# POTENCIOMETRO.net
KiCad netlist of a schematic drawn in EAGLE
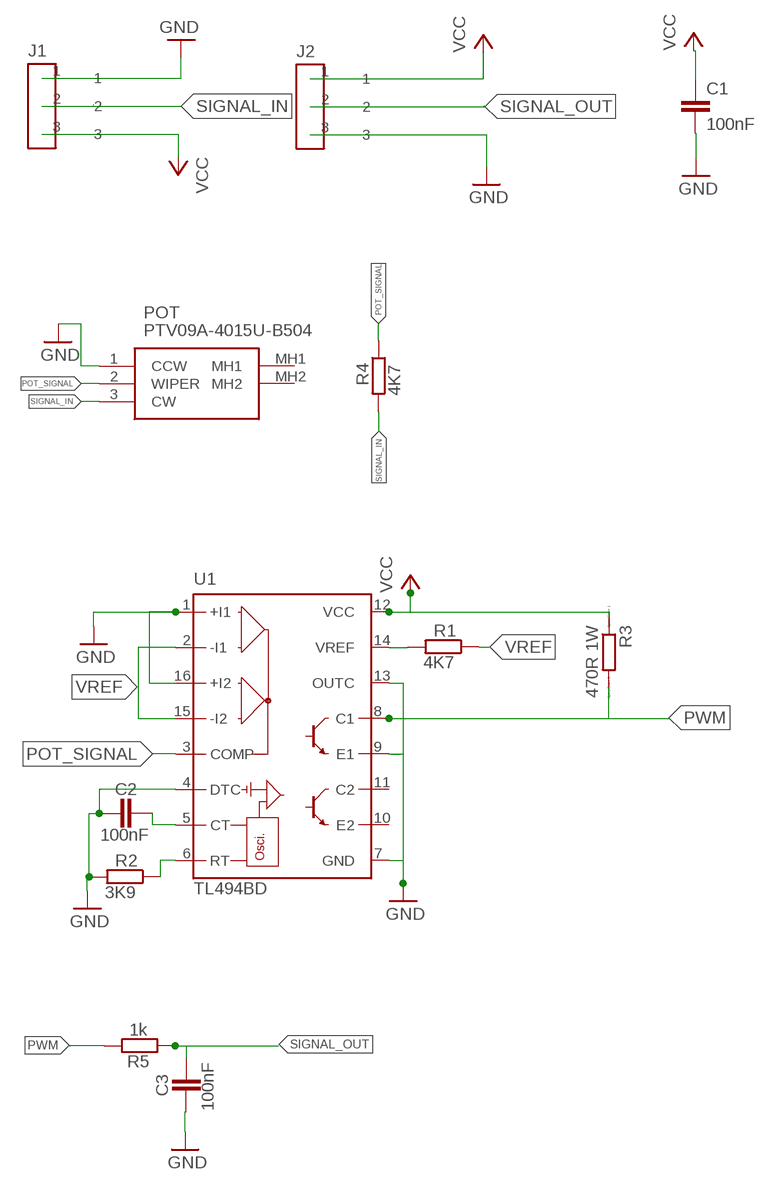
[diagram p0: schematic, sheet 1]

(export (version "E")
  (design (tool "Eeschema 10.0.6"))
  (components
    (comp (ref "C1")
      (value "100nF")
      (footprint "eagle-import:C0805")
      (libsource (lib "eagle-import") (part "C-EUC0805"))
    )
    (comp (ref "C2")
      (value "100nF")
      (footprint "eagle-import:C0805")
      (libsource (lib "eagle-import") (part "C-EUC0805"))
    )
    (comp (ref "C3")
      (value "100nF")
      (footprint "eagle-import:C0805")
      (libsource (lib "eagle-import") (part "C-EUC0805"))
    )
    (comp (ref "J1")
      (value "CONECTOR_MACHO")
      (footprint "eagle-import:3CONECTOR")
      (libsource (lib "eagle-import") (part "CONECTOR_MACHO"))
    )
    (comp (ref "J2")
      (value "CONECTOR_FEMEA")
      (footprint "eagle-import:3CONECTOR")
      (libsource (lib "eagle-import") (part "CONECTOR_FEMEA"))
    )
    (comp (ref "POT")
      (value "PTV09A-4015U-B504")
      (footprint "eagle-import:PTV09A4015UB104")
      (fields (field (name "MOUSER_PART_NUMBER") "652-PTV09A-4015UB504"))
      (libsource (lib "eagle-import") (part "PTV09A-4015U-B504"))
    )
    (comp (ref "R1")
      (value "4K7")
      (footprint "eagle-import:R0805W")
      (libsource (lib "eagle-import") (part "R-EU_R0805W"))
    )
    (comp (ref "R2")
      (value "3K9")
      (footprint "eagle-import:R0805W")
      (libsource (lib "eagle-import") (part "R-EU_R0805W"))
    )
    (comp (ref "R3")
      (value "470R 1W")
      (footprint "eagle-import:R2512")
      (libsource (lib "eagle-import") (part "RR2512"))
    )
    (comp (ref "R4")
      (value "4K7")
      (footprint "eagle-import:R0805W")
      (libsource (lib "eagle-import") (part "R-EU_R0805W"))
    )
    (comp (ref "R5")
      (value "1k")
      (footprint "eagle-import:R0805W")
      (libsource (lib "eagle-import") (part "R-EU_R0805W"))
    )
    (comp (ref "U1")
      (value "TL494BD")
      (footprint "eagle-import:SO16")
      (libsource (lib "eagle-import") (part "TL494DB"))
    )
  )
  (nets
    (net (code "1") (name "GND") (class "Default")
      (node (ref "C1") (pin "2") (pinfunction "2_2") (pintype "passive"))
      (node (ref "C2") (pin "1") (pinfunction "1_1") (pintype "passive"))
      (node (ref "C3") (pin "1") (pinfunction "1_1") (pintype "passive"))
      (node (ref "J1") (pin "1") (pinfunction "1_1") (pintype "bidirectional"))
      (node (ref "J2") (pin "3") (pinfunction "3_3") (pintype "bidirectional"))
      (node (ref "POT") (pin "1") (pinfunction "CCW_1") (pintype "bidirectional"))
      (node (ref "R2") (pin "2") (pinfunction "2_2") (pintype "passive"))
      (node (ref "U1") (pin "1") (pinfunction "+I1_1") (pintype "input"))
      (node (ref "U1") (pin "13") (pinfunction "OUTC_13") (pintype "output"))
      (node (ref "U1") (pin "16") (pinfunction "+I2_16") (pintype "input"))
      (node (ref "U1") (pin "4") (pinfunction "DTC_4") (pintype "input"))
      (node (ref "U1") (pin "7") (pinfunction "GND_7") (pintype "power_in"))
      (node (ref "U1") (pin "9") (pinfunction "E1_9") (pintype "passive"))
    )
    (net (code "2") (name "Net-(U1-CT)") (class "Default")
      (node (ref "C2") (pin "2") (pinfunction "2_2") (pintype "passive"))
      (node (ref "U1") (pin "5") (pinfunction "CT_5") (pintype "input"))
    )
    (net (code "3") (name "Net-(U1-RT)") (class "Default")
      (node (ref "R2") (pin "1") (pinfunction "1_1") (pintype "passive"))
      (node (ref "U1") (pin "6") (pinfunction "RT_6") (pintype "input"))
    )
    (net (code "4") (name "Net-(U1-VREF)") (class "Default")
      (node (ref "R1") (pin "2") (pinfunction "2_2") (pintype "passive"))
      (node (ref "U1") (pin "14") (pinfunction "VREF_14") (pintype "input"))
    )
    (net (code "5") (name "POT_SIGNAL") (class "Default")
      (node (ref "POT") (pin "2") (pinfunction "WIPER_2") (pintype "bidirectional"))
      (node (ref "R4") (pin "1") (pinfunction "1_1") (pintype "passive"))
      (node (ref "U1") (pin "3") (pinfunction "COMP_3") (pintype "passive"))
    )
    (net (code "6") (name "PWM") (class "Default")
      (node (ref "R3") (pin "2") (pinfunction "2_2") (pintype "passive"))
      (node (ref "R5") (pin "1") (pinfunction "1_1") (pintype "passive"))
      (node (ref "U1") (pin "8") (pinfunction "C1_8") (pintype "passive"))
    )
    (net (code "7") (name "SIGNAL_IN") (class "Default")
      (node (ref "J1") (pin "2") (pinfunction "2_2") (pintype "bidirectional"))
      (node (ref "POT") (pin "3") (pinfunction "CW_3") (pintype "bidirectional"))
      (node (ref "R4") (pin "2") (pinfunction "2_2") (pintype "passive"))
    )
    (net (code "8") (name "SIGNAL_OUT") (class "Default")
      (node (ref "C3") (pin "2") (pinfunction "2_2") (pintype "passive"))
      (node (ref "J2") (pin "2") (pinfunction "2_2") (pintype "bidirectional"))
      (node (ref "R5") (pin "2") (pinfunction "2_2") (pintype "passive"))
    )
    (net (code "9") (name "VCC") (class "Default")
      (node (ref "C1") (pin "1") (pinfunction "1_1") (pintype "passive"))
      (node (ref "J1") (pin "3") (pinfunction "3_3") (pintype "bidirectional"))
      (node (ref "J2") (pin "1") (pinfunction "1_1") (pintype "bidirectional"))
      (node (ref "R3") (pin "1") (pinfunction "1_1") (pintype "passive"))
      (node (ref "U1") (pin "12") (pinfunction "VCC_12") (pintype "power_in"))
    )
    (net (code "10") (name "VREF") (class "Default")
      (node (ref "R1") (pin "1") (pinfunction "1_1") (pintype "passive"))
      (node (ref "U1") (pin "15") (pinfunction "-I2_15") (pintype "input"))
      (node (ref "U1") (pin "2") (pinfunction "-I1_2") (pintype "input"))
    )
    (net (code "11") (name "unconnected-(POT-PadMH1)") (class "Default")
      (node (ref "POT") (pin "MH1") (pinfunction "MH1_MH1") (pintype "bidirectional"))
    )
    (net (code "12") (name "unconnected-(POT-PadMH2)") (class "Default")
      (node (ref "POT") (pin "MH2") (pinfunction "MH2_MH2") (pintype "bidirectional"))
    )
    (net (code "13") (name "unconnected-(U1-C2-Pad11)") (class "Default")
      (node (ref "U1") (pin "11") (pinfunction "C2_11") (pintype "passive"))
    )
    (net (code "14") (name "unconnected-(U1-E2-Pad10)") (class "Default")
      (node (ref "U1") (pin "10") (pinfunction "E2_10") (pintype "passive"))
    )
  )
)
